# 06_-POWER_SUPPLY.net
KiCad netlist of a schematic drawn in Altium Designer
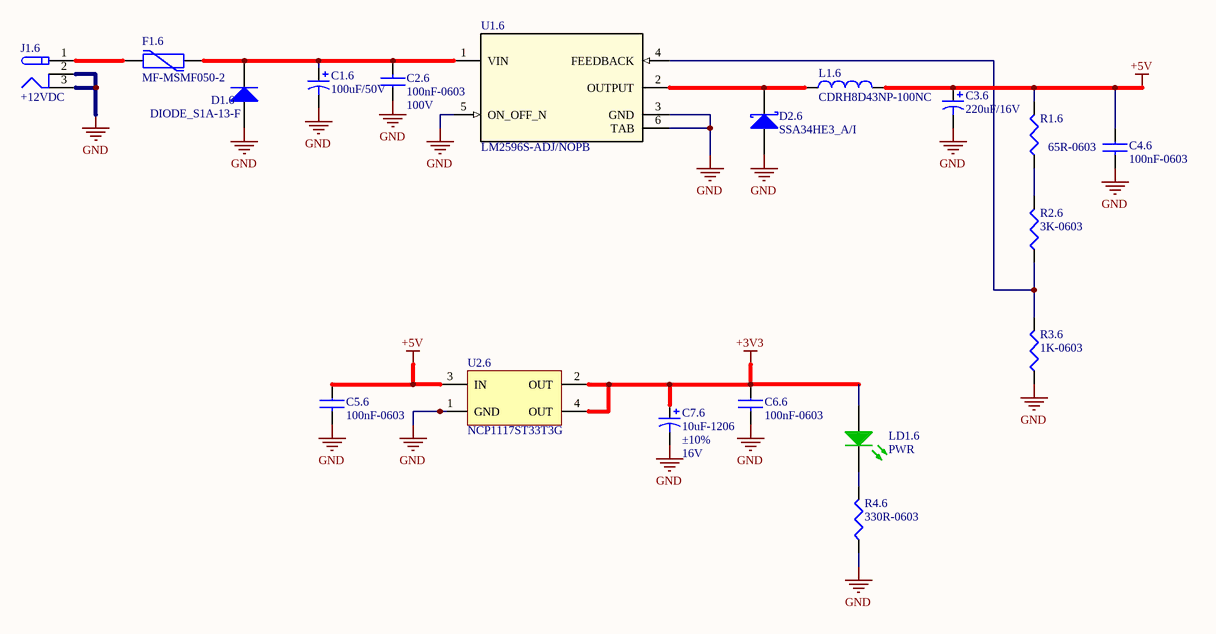
[diagram p0: [06]-POWER_SUPPLY.SchDoc]

(export (version "E")
  (design (tool "Eeschema 10.0.6"))
  (components
    (comp (ref "C1.6")
      (value "100uF/50V")
      (footprint "MinhTien_PcbLib:CAPPR5-10x16")
      (description "Polarized Capacitor")
      (fields (field (name "Comment") "Cap Polar") (field (name "PUBLISHER") "Altium Limited"))
      (libsource (lib "MinhTien_SCHLib") (part "Cap Polar"))
    )
    (comp (ref "C2.6")
      (value "100nF-0603")
      (footprint "CAP0603")
      (description "CAP CER 0.1UF 100V X7R 0603")
      (fields
        (field (name "MANUFACTURER") "Yageo")
        (field (name "MANUFACTURER PART NUMBER") "CC0603KRX7R0BB104")
        (field (name "VOLTAGE - RATED") "100V")
      )
      (libsource (lib "Indruino") (part "CC0603KRX7R0BB104"))
    )
    (comp (ref "C3.6")
      (value "220uF/16V")
      (footprint "MinhTien_PcbLib:CAPPR5-10x16")
      (description "Polarized Capacitor")
      (fields (field (name "Comment") "Cap Polar") (field (name "PUBLISHER") "Altium Limited"))
      (libsource (lib "MinhTien_SCHLib") (part "Cap Polar"))
    )
    (comp (ref "C4.6")
      (value "100nF-0603")
      (footprint "CAP0603")
      (description "CAP CER 0.1UF 50V X7R 0603")
      (fields (field (name "TOLERANCE") "±10%"))
      (libsource (lib "Indruino") (part "CC0603KRX7R9BB104"))
    )
    (comp (ref "C5.6")
      (value "100nF-0603")
      (footprint "CAP0603")
      (description "CAP CER 0.1UF 50V X7R 0603")
      (fields (field (name "TOLERANCE") "±10%"))
      (libsource (lib "Indruino") (part "CC0603KRX7R9BB104"))
    )
    (comp (ref "C6.6")
      (value "100nF-0603")
      (footprint "CAP0603")
      (description "CAP CER 0.1UF 50V X7R 0603")
      (fields (field (name "TOLERANCE") "±10%"))
      (libsource (lib "Indruino") (part "CC0603KRX7R9BB104"))
    )
    (comp (ref "C7.6")
      (value "10uF-1206")
      (footprint "CAP1206_TANTALUM_YELLOW")
      (description "CAP TANT 10UF 16V 10% 1206")
      (fields (field (name "TOLERANCE") "±10%") (field (name "VOLTAGE - RATED") "16V"))
      (libsource (lib "Indruino") (part "T491A106K016AT"))
    )
    (comp (ref "D1.6")
      (value "DIODE_S1A-13-F")
      (footprint "DO-214AC")
      (description "DIODE GEN PURP 50V 1A SMA")
      (fields
        (field (name "MANUFACTURER") "Diodes Incorporated")
        (field (name "MANUFACTURER PART NUMBER") "S1A-13-F")
      )
      (libsource (lib "Indruino") (part "DIODE_S1A-13-F"))
    )
    (comp (ref "D2.6")
      (value "SSA34HE3_A/I")
      (footprint "Indruino:DO-214AC")
      (description "DIODE SCHOTTKY 40V 3A DO214AC")
      (libsource (lib "Indruino") (part "DIODE_SSA34HE3_A/I"))
    )
    (comp (ref "F1.6")
      (value "MF-MSMF050-2")
      (footprint "Indruino:FUSE_PTC_SMD1812_02")
      (description "Resettable Fuses - PPTC 0.50A 15V 0.15ohm AE C-Q200")
      (fields (field (name "MANUFACTURER") "Bourns"))
      (libsource (lib "Indruino") (part "FUSE_MF-MSMF050-2"))
    )
    (comp (ref "J1.6")
      (value "+12VDC")
      (footprint "AZ_Lib:DCIN_5.5/2.1")
      (libsource (lib "AZ_Lib") (part "DCIN_5.5/2.1"))
    )
    (comp (ref "L1.6")
      (value "CDRH8D43NP-100NC")
      (footprint "INDC_CDRH8D43")
      (description "FIXED IND 10UH 3.2A 36 MOHM SMD")
      (fields
        (field (name "MANUFACTURER") "Sumida America Components Inc.")
        (field (name "TOLERANCE") "±30%")
      )
      (libsource (lib "Indruino") (part "IND_CDRH8D43NP-100NC"))
    )
    (comp (ref "LD1.6")
      (value "PWR")
      (footprint "Indruino:LED_SMD0603_GREEN")
      (description "LED GREEN CLEAR 0603 SMD")
      (libsource (lib "Indruino") (part "LED_LTST-C191KGKT"))
    )
    (comp (ref "R1.6")
      (value "65R-0603")
      (footprint "RES0603")
      (description "RES SMD 22 OHM 5% 1/10W 0603")
      (fields (field (name "TOLERANCE") "±5%"))
      (libsource (lib "Indruino") (part "RC0603JR-0722RL"))
    )
    (comp (ref "R2.6")
      (value "3K-0603")
      (footprint "RES0603")
      (description "Thick Film Resistors - SMD 3.3K OHM 5%")
      (fields
        (field (name "MANUFACTURER") "Yageo")
        (field (name "MANUFACTURER PART NUMBER") "RC0603JR-073K3L")
      )
      (libsource (lib "Indruino") (part "RC0603JR-073K3L"))
    )
    (comp (ref "R3.6")
      (value "1K-0603")
      (footprint "RES0603")
      (description "RES SMD 1K OHM 5% 1/10W 0603")
      (fields (field (name "TOLERANCE") "±5%"))
      (libsource (lib "Indruino") (part "RC0603JR-071KL"))
    )
    (comp (ref "R4.6")
      (value "330R-0603")
      (footprint "RES0603")
      (description "RES SMD 330 OHM 5% 1/10W 0603")
      (fields (field (name "TOLERANCE") "±5%"))
      (libsource (lib "Indruino") (part "RC0603JR-07330RL"))
    )
    (comp (ref "U1.6")
      (value "LM2596S-ADJ/NOPB")
      (footprint "AZ_Lib:TO-263-5")
      (description "No Description Available")
      (fields
        (field (name "PARTNUMBER") "LM2596SX-ADJ/NOPB")
        (field (name "MANUFACTURER") "Texas Instruments")
        (field (name "COPYRIGHT") "Copyright (C) 2021 Ultra Librarian. All rights reserved.")
      )
      (libsource (lib "AZ_Lib") (part "LM2596S-ADJ/NOPB"))
    )
    (comp (ref "U2.6")
      (value "NCP1117ST33T3G")
      (footprint "Indruino:SOT223-4M_AMS1117_3V3")
      (description "LDO Voltage Regulators 3.3V 1A Positive")
      (fields (field (name "MANUFACTURER") "ON Semiconductor"))
      (libsource (lib "Indruino") (part "NCP1117ST33T3G"))
    )
  )
  (nets
    (net (code "1") (name "+3V3") (class "Default")
      (node (ref "C6.6") (pin "1") (pinfunction "1_1") (pintype "passive"))
      (node (ref "C7.6") (pin "1") (pinfunction "1_1") (pintype "passive"))
      (node (ref "LD1.6") (pin "1") (pinfunction "A_1") (pintype "passive"))
      (node (ref "U2.6") (pin "2") (pinfunction "OUT_2") (pintype "passive"))
      (node (ref "U2.6") (pin "4") (pinfunction "OUT_4") (pintype "passive"))
    )
    (net (code "2") (name "+5V") (class "Default")
      (node (ref "C3.6") (pin "1") (pinfunction "1_1") (pintype "passive"))
      (node (ref "C4.6") (pin "1") (pinfunction "1_1") (pintype "passive"))
      (node (ref "C5.6") (pin "1") (pinfunction "1_1") (pintype "passive"))
      (node (ref "L1.6") (pin "2") (pinfunction "2_2") (pintype "passive"))
      (node (ref "R1.6") (pin "2") (pinfunction "2_2") (pintype "passive"))
      (node (ref "U2.6") (pin "3") (pinfunction "IN_3") (pintype "power_in"))
    )
    (net (code "3") (name "GND") (class "Default")
      (node (ref "C1.6") (pin "2") (pinfunction "2_2") (pintype "passive"))
      (node (ref "C2.6") (pin "1") (pinfunction "1_1") (pintype "passive"))
      (node (ref "C3.6") (pin "2") (pinfunction "2_2") (pintype "passive"))
      (node (ref "C4.6") (pin "2") (pinfunction "2_2") (pintype "passive"))
      (node (ref "C5.6") (pin "2") (pinfunction "2_2") (pintype "passive"))
      (node (ref "C6.6") (pin "2") (pinfunction "2_2") (pintype "passive"))
      (node (ref "C7.6") (pin "2") (pinfunction "2_2") (pintype "passive"))
      (node (ref "D1.6") (pin "1") (pinfunction "A_1") (pintype "passive"))
      (node (ref "D2.6") (pin "1") (pinfunction "A_1") (pintype "passive"))
      (node (ref "J1.6") (pin "2") (pinfunction "NC_2") (pintype "passive"))
      (node (ref "J1.6") (pin "3") (pinfunction "-_3") (pintype "passive"))
      (node (ref "R3.6") (pin "1") (pinfunction "1_1") (pintype "passive"))
      (node (ref "R4.6") (pin "1") (pinfunction "1_1") (pintype "passive"))
      (node (ref "U1.6") (pin "3") (pinfunction "GND_3") (pintype "power_in"))
      (node (ref "U1.6") (pin "5") (pinfunction "ON_OFF_N_5") (pintype "input"))
      (node (ref "U1.6") (pin "6") (pinfunction "TAB_6") (pintype "power_in"))
      (node (ref "U2.6") (pin "1") (pinfunction "GND_1") (pintype "power_in"))
    )
    (net (code "4") (name "Net-(D1.6-K)") (class "Default")
      (node (ref "C1.6") (pin "1") (pinfunction "1_1") (pintype "passive"))
      (node (ref "C2.6") (pin "2") (pinfunction "2_2") (pintype "passive"))
      (node (ref "D1.6") (pin "2") (pinfunction "K_2") (pintype "passive"))
      (node (ref "F1.6") (pin "2") (pinfunction "2_2") (pintype "passive"))
      (node (ref "U1.6") (pin "1") (pinfunction "VIN_1") (pintype "power_in"))
    )
    (net (code "5") (name "Net-(D2.6-K)") (class "Default")
      (node (ref "D2.6") (pin "2") (pinfunction "K_2") (pintype "passive"))
      (node (ref "L1.6") (pin "1") (pinfunction "1_1") (pintype "passive"))
      (node (ref "U1.6") (pin "2") (pinfunction "OUTPUT_2") (pintype "power_in"))
    )
    (net (code "6") (name "Net-(J1.6-+)") (class "Default")
      (node (ref "F1.6") (pin "1") (pinfunction "1_1") (pintype "passive"))
      (node (ref "J1.6") (pin "1") (pinfunction "+_1") (pintype "passive"))
    )
    (net (code "7") (name "Net-(LD1.6-K)") (class "Default")
      (node (ref "LD1.6") (pin "2") (pinfunction "K_2") (pintype "passive"))
      (node (ref "R4.6") (pin "2") (pinfunction "2_2") (pintype "passive"))
    )
    (net (code "8") (name "Net-(R1.6-Pad1)") (class "Default")
      (node (ref "R1.6") (pin "1") (pinfunction "1_1") (pintype "passive"))
      (node (ref "R2.6") (pin "2") (pinfunction "2_2") (pintype "passive"))
    )
    (net (code "9") (name "Net-(U1.6-FEEDBACK)") (class "Default")
      (node (ref "R2.6") (pin "1") (pinfunction "1_1") (pintype "passive"))
      (node (ref "R3.6") (pin "2") (pinfunction "2_2") (pintype "passive"))
      (node (ref "U1.6") (pin "4") (pinfunction "FEEDBACK_4") (pintype "input"))
    )
  )
)
